# a201-kill-eq.net
KiCad netlist of a schematic drawn in EAGLE
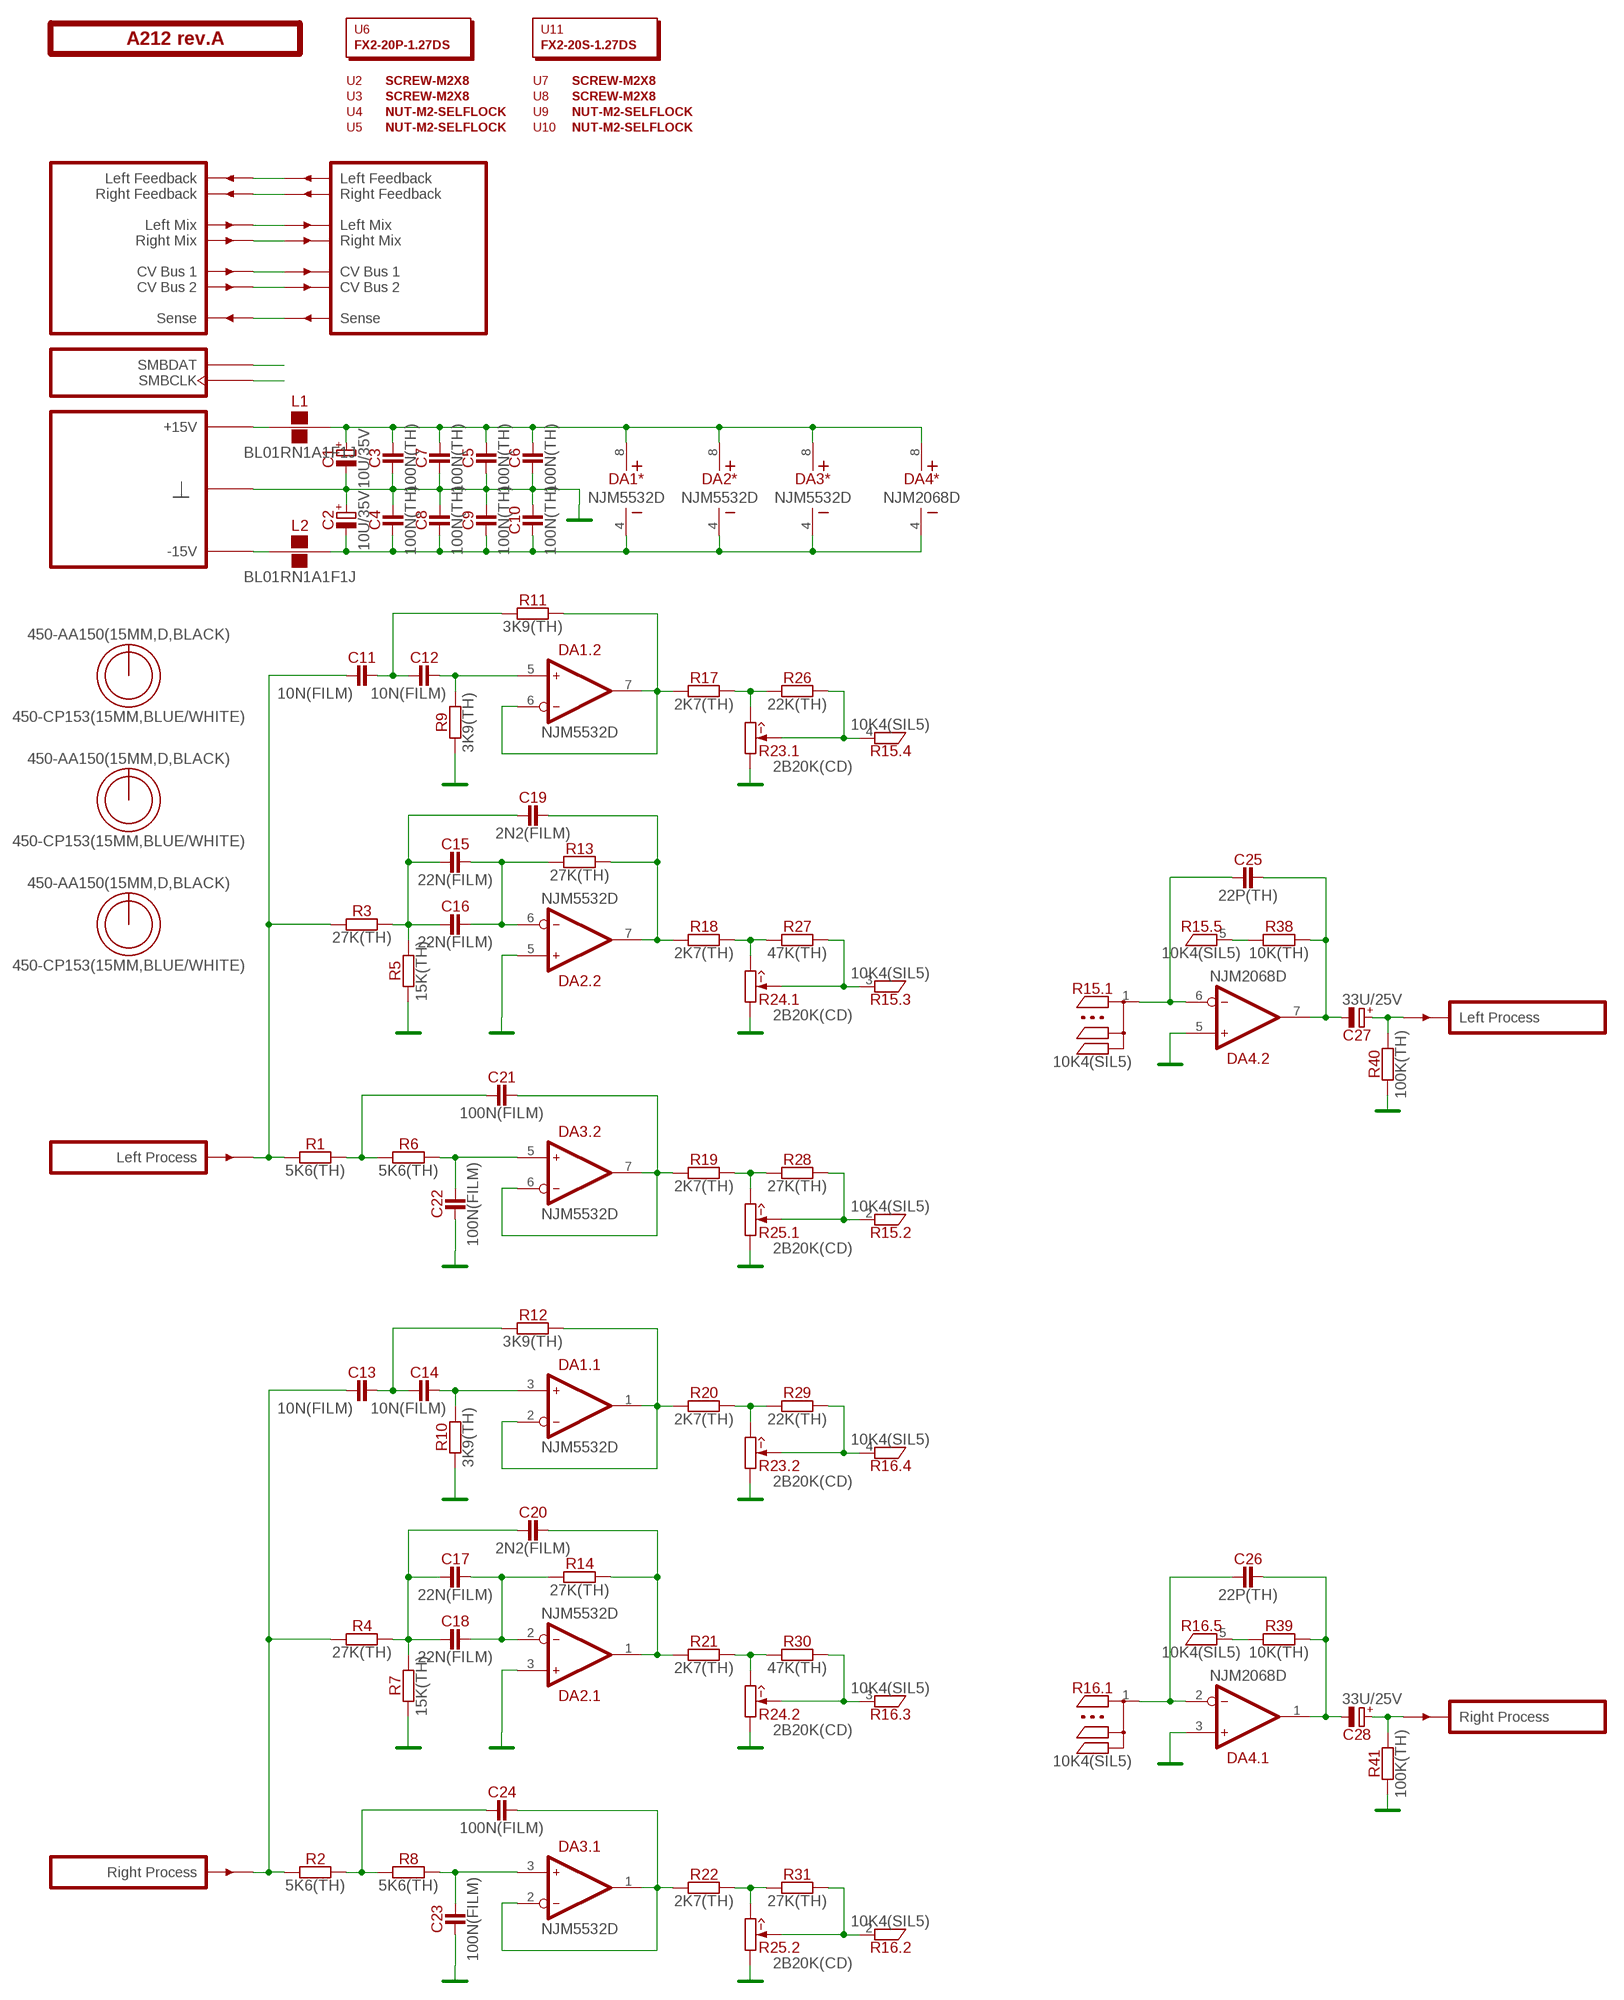
[diagram p0: schematic, sheet 1]

(export (version "E")
  (design (tool "Eeschema 10.0.6"))
  (components
    (comp (ref "C1")
      (value "10U/35V")
      (footprint "eagle-import:E2-5")
      (libsource (lib "eagle-import") (part "?10U/35V"))
    )
    (comp (ref "C2")
      (value "10U/35V")
      (footprint "eagle-import:E2-5")
      (libsource (lib "eagle-import") (part "?10U/35V"))
    )
    (comp (ref "C3")
      (value "100N(TH)")
      (footprint "eagle-import:C050-024X044")
      (libsource (lib "eagle-import") (part "?100N(TH)"))
    )
    (comp (ref "C4")
      (value "100N(TH)")
      (footprint "eagle-import:C050-024X044")
      (libsource (lib "eagle-import") (part "?100N(TH)"))
    )
    (comp (ref "C5")
      (value "100N(TH)")
      (footprint "eagle-import:C050-024X044")
      (libsource (lib "eagle-import") (part "?100N(TH)"))
    )
    (comp (ref "C6")
      (value "100N(TH)")
      (footprint "eagle-import:C050-024X044")
      (libsource (lib "eagle-import") (part "?100N(TH)"))
    )
    (comp (ref "C7")
      (value "100N(TH)")
      (footprint "eagle-import:C050-024X044")
      (libsource (lib "eagle-import") (part "?100N(TH)"))
    )
    (comp (ref "C8")
      (value "100N(TH)")
      (footprint "eagle-import:C050-024X044")
      (libsource (lib "eagle-import") (part "?100N(TH)"))
    )
    (comp (ref "C9")
      (value "100N(TH)")
      (footprint "eagle-import:C050-024X044")
      (libsource (lib "eagle-import") (part "?100N(TH)"))
    )
    (comp (ref "C10")
      (value "100N(TH)")
      (footprint "eagle-import:C050-024X044")
      (libsource (lib "eagle-import") (part "?100N(TH)"))
    )
    (comp (ref "C11")
      (value "10N(FILM)")
      (footprint "eagle-import:C050-025X075")
      (libsource (lib "eagle-import") (part "?10N(FILM)"))
    )
    (comp (ref "C12")
      (value "10N(FILM)")
      (footprint "eagle-import:C050-025X075")
      (libsource (lib "eagle-import") (part "?10N(FILM)"))
    )
    (comp (ref "C13")
      (value "10N(FILM)")
      (footprint "eagle-import:C050-025X075")
      (libsource (lib "eagle-import") (part "?10N(FILM)"))
    )
    (comp (ref "C14")
      (value "10N(FILM)")
      (footprint "eagle-import:C050-025X075")
      (libsource (lib "eagle-import") (part "?10N(FILM)"))
    )
    (comp (ref "C15")
      (value "22N(FILM)")
      (footprint "eagle-import:C050-025X075")
      (libsource (lib "eagle-import") (part "?22N(FILM)"))
    )
    (comp (ref "C16")
      (value "22N(FILM)")
      (footprint "eagle-import:C050-025X075")
      (libsource (lib "eagle-import") (part "?22N(FILM)"))
    )
    (comp (ref "C17")
      (value "22N(FILM)")
      (footprint "eagle-import:C050-025X075")
      (libsource (lib "eagle-import") (part "?22N(FILM)"))
    )
    (comp (ref "C18")
      (value "22N(FILM)")
      (footprint "eagle-import:C050-025X075")
      (libsource (lib "eagle-import") (part "?22N(FILM)"))
    )
    (comp (ref "C19")
      (value "2N2(FILM)")
      (footprint "eagle-import:C050-025X075")
      (libsource (lib "eagle-import") (part "?2N2(FILM)"))
    )
    (comp (ref "C20")
      (value "2N2(FILM)")
      (footprint "eagle-import:C050-025X075")
      (libsource (lib "eagle-import") (part "?2N2(FILM)"))
    )
    (comp (ref "C21")
      (value "100N(FILM)")
      (footprint "eagle-import:C050-025X075")
      (libsource (lib "eagle-import") (part "?100N(FILM)"))
    )
    (comp (ref "C22")
      (value "100N(FILM)")
      (footprint "eagle-import:C050-025X075")
      (libsource (lib "eagle-import") (part "?100N(FILM)"))
    )
    (comp (ref "C23")
      (value "100N(FILM)")
      (footprint "eagle-import:C050-025X075")
      (libsource (lib "eagle-import") (part "?100N(FILM)"))
    )
    (comp (ref "C24")
      (value "100N(FILM)")
      (footprint "eagle-import:C050-025X075")
      (libsource (lib "eagle-import") (part "?100N(FILM)"))
    )
    (comp (ref "C25")
      (value "22P(TH)")
      (footprint "eagle-import:C050-024X044")
      (libsource (lib "eagle-import") (part "?22P(TH)"))
    )
    (comp (ref "C26")
      (value "22P(TH)")
      (footprint "eagle-import:C050-024X044")
      (libsource (lib "eagle-import") (part "?22P(TH)"))
    )
    (comp (ref "C27")
      (value "33U/25V")
      (footprint "eagle-import:E2,5-7")
      (libsource (lib "eagle-import") (part "?33U/25V"))
    )
    (comp (ref "C28")
      (value "33U/25V")
      (footprint "eagle-import:E2,5-7")
      (libsource (lib "eagle-import") (part "?33U/25V"))
    )
    (comp (ref "DA1")
      (value "NJM5532D")
      (footprint "eagle-import:DIP-8")
      (libsource (lib "eagle-import") (part "NJM5532D"))
    )
    (comp (ref "DA2")
      (value "NJM5532D")
      (footprint "eagle-import:DIP-8")
      (libsource (lib "eagle-import") (part "NJM5532D"))
    )
    (comp (ref "DA3")
      (value "NJM5532D")
      (footprint "eagle-import:DIP-8")
      (libsource (lib "eagle-import") (part "NJM5532D"))
    )
    (comp (ref "DA4")
      (value "NJM2068D")
      (footprint "eagle-import:DIP-8")
      (libsource (lib "eagle-import") (part "NJM2068D"))
    )
    (comp (ref "L1")
      (value "BL01RN1A1F1J")
      (footprint "eagle-import:BL01RN1A")
      (libsource (lib "eagle-import") (part "BL01RN1A?1F1J"))
    )
    (comp (ref "L2")
      (value "BL01RN1A1F1J")
      (footprint "eagle-import:BL01RN1A")
      (libsource (lib "eagle-import") (part "BL01RN1A?1F1J"))
    )
    (comp (ref "O1")
      (value "450-AA150(15MM,D,BLACK)")
      (footprint "eagle-import:EMPTY")
      (libsource (lib "eagle-import") (part "450-AA?150(15MM,D,BLACK)"))
    )
    (comp (ref "O2")
      (value "450-AA150(15MM,D,BLACK)")
      (footprint "eagle-import:EMPTY")
      (libsource (lib "eagle-import") (part "450-AA?150(15MM,D,BLACK)"))
    )
    (comp (ref "O3")
      (value "450-AA150(15MM,D,BLACK)")
      (footprint "eagle-import:EMPTY")
      (libsource (lib "eagle-import") (part "450-AA?150(15MM,D,BLACK)"))
    )
    (comp (ref "O4")
      (value "450-CP153(15MM,BLUE/WHITE)")
      (footprint "eagle-import:EMPTY")
      (libsource (lib "eagle-import") (part "450-C?P153(15MM,BLUE/WHITE)"))
    )
    (comp (ref "O5")
      (value "450-CP153(15MM,BLUE/WHITE)")
      (footprint "eagle-import:EMPTY")
      (libsource (lib "eagle-import") (part "450-C?P153(15MM,BLUE/WHITE)"))
    )
    (comp (ref "O6")
      (value "450-CP153(15MM,BLUE/WHITE)")
      (footprint "eagle-import:EMPTY")
      (libsource (lib "eagle-import") (part "450-C?P153(15MM,BLUE/WHITE)"))
    )
    (comp (ref "PCB1")
      (value "A212 rev.A")
      (footprint "eagle-import:ST2-BOARD-50")
      (libsource (lib "eagle-import") (part "ST2-BOARD-?50"))
    )
    (comp (ref "R1")
      (value "5K6(TH)")
      (footprint "eagle-import:R-0207_10")
      (libsource (lib "eagle-import") (part "?5K6(TH)"))
    )
    (comp (ref "R2")
      (value "5K6(TH)")
      (footprint "eagle-import:R-0207_10")
      (libsource (lib "eagle-import") (part "?5K6(TH)"))
    )
    (comp (ref "R3")
      (value "27K(TH)")
      (footprint "eagle-import:R-0207_10")
      (libsource (lib "eagle-import") (part "?27K(TH)"))
    )
    (comp (ref "R4")
      (value "27K(TH)")
      (footprint "eagle-import:R-0207_10")
      (libsource (lib "eagle-import") (part "?27K(TH)"))
    )
    (comp (ref "R5")
      (value "15K(TH)")
      (footprint "eagle-import:R-0207_10")
      (libsource (lib "eagle-import") (part "?15K(TH)"))
    )
    (comp (ref "R6")
      (value "5K6(TH)")
      (footprint "eagle-import:R-0207_10")
      (libsource (lib "eagle-import") (part "?5K6(TH)"))
    )
    (comp (ref "R7")
      (value "15K(TH)")
      (footprint "eagle-import:R-0207_10")
      (libsource (lib "eagle-import") (part "?15K(TH)"))
    )
    (comp (ref "R8")
      (value "5K6(TH)")
      (footprint "eagle-import:R-0207_10")
      (libsource (lib "eagle-import") (part "?5K6(TH)"))
    )
    (comp (ref "R9")
      (value "3K9(TH)")
      (footprint "eagle-import:R-0207_10")
      (libsource (lib "eagle-import") (part "?3K9(TH)"))
    )
    (comp (ref "R10")
      (value "3K9(TH)")
      (footprint "eagle-import:R-0207_10")
      (libsource (lib "eagle-import") (part "?3K9(TH)"))
    )
    (comp (ref "R11")
      (value "3K9(TH)")
      (footprint "eagle-import:R-0207_10")
      (libsource (lib "eagle-import") (part "?3K9(TH)"))
    )
    (comp (ref "R12")
      (value "3K9(TH)")
      (footprint "eagle-import:R-0207_10")
      (libsource (lib "eagle-import") (part "?3K9(TH)"))
    )
    (comp (ref "R13")
      (value "27K(TH)")
      (footprint "eagle-import:R-0207_10")
      (libsource (lib "eagle-import") (part "?27K(TH)"))
    )
    (comp (ref "R14")
      (value "27K(TH)")
      (footprint "eagle-import:R-0207_10")
      (libsource (lib "eagle-import") (part "?27K(TH)"))
    )
    (comp (ref "R15")
      (value "10K4(SIL5)")
      (footprint "eagle-import:R-SIL5")
      (libsource (lib "eagle-import") (part "?4(SIL5)10K"))
    )
    (comp (ref "R16")
      (value "10K4(SIL5)")
      (footprint "eagle-import:R-SIL5")
      (libsource (lib "eagle-import") (part "?4(SIL5)10K"))
    )
    (comp (ref "R17")
      (value "2K7(TH)")
      (footprint "eagle-import:R-0207_10")
      (libsource (lib "eagle-import") (part "?2K7(TH)"))
    )
    (comp (ref "R18")
      (value "2K7(TH)")
      (footprint "eagle-import:R-0207_10")
      (libsource (lib "eagle-import") (part "?2K7(TH)"))
    )
    (comp (ref "R19")
      (value "2K7(TH)")
      (footprint "eagle-import:R-0207_10")
      (libsource (lib "eagle-import") (part "?2K7(TH)"))
    )
    (comp (ref "R20")
      (value "2K7(TH)")
      (footprint "eagle-import:R-0207_10")
      (libsource (lib "eagle-import") (part "?2K7(TH)"))
    )
    (comp (ref "R21")
      (value "2K7(TH)")
      (footprint "eagle-import:R-0207_10")
      (libsource (lib "eagle-import") (part "?2K7(TH)"))
    )
    (comp (ref "R22")
      (value "2K7(TH)")
      (footprint "eagle-import:R-0207_10")
      (libsource (lib "eagle-import") (part "?2K7(TH)"))
    )
    (comp (ref "R23")
      (value "2B20K(CD)")
      (footprint "eagle-import:RV11-DUAL")
      (libsource (lib "eagle-import") (part "2?B20K(CD)"))
    )
    (comp (ref "R24")
      (value "2B20K(CD)")
      (footprint "eagle-import:RV11-DUAL")
      (libsource (lib "eagle-import") (part "2?B20K(CD)"))
    )
    (comp (ref "R25")
      (value "2B20K(CD)")
      (footprint "eagle-import:RV11-DUAL")
      (libsource (lib "eagle-import") (part "2?B20K(CD)"))
    )
    (comp (ref "R26")
      (value "22K(TH)")
      (footprint "eagle-import:R-0207_10")
      (libsource (lib "eagle-import") (part "?22K(TH)"))
    )
    (comp (ref "R27")
      (value "47K(TH)")
      (footprint "eagle-import:R-0207_10")
      (libsource (lib "eagle-import") (part "?47K(TH)"))
    )
    (comp (ref "R28")
      (value "27K(TH)")
      (footprint "eagle-import:R-0207_10")
      (libsource (lib "eagle-import") (part "?27K(TH)"))
    )
    (comp (ref "R29")
      (value "22K(TH)")
      (footprint "eagle-import:R-0207_10")
      (libsource (lib "eagle-import") (part "?22K(TH)"))
    )
    (comp (ref "R30")
      (value "47K(TH)")
      (footprint "eagle-import:R-0207_10")
      (libsource (lib "eagle-import") (part "?47K(TH)"))
    )
    (comp (ref "R31")
      (value "27K(TH)")
      (footprint "eagle-import:R-0207_10")
      (libsource (lib "eagle-import") (part "?27K(TH)"))
    )
    (comp (ref "R38")
      (value "10K(TH)")
      (footprint "eagle-import:R-0207_10")
      (libsource (lib "eagle-import") (part "?10K(TH)"))
    )
    (comp (ref "R39")
      (value "10K(TH)")
      (footprint "eagle-import:R-0207_10")
      (libsource (lib "eagle-import") (part "?10K(TH)"))
    )
    (comp (ref "R40")
      (value "100K(TH)")
      (footprint "eagle-import:R-0207_10")
      (libsource (lib "eagle-import") (part "?100K(TH)"))
    )
    (comp (ref "R41")
      (value "100K(TH)")
      (footprint "eagle-import:R-0207_10")
      (libsource (lib "eagle-import") (part "?100K(TH)"))
    )
    (comp (ref "U2")
      (value "SCREW-M2X8")
      (footprint "eagle-import:EMPTY")
      (libsource (lib "eagle-import") (part "?SCREW-M2X8"))
    )
    (comp (ref "U3")
      (value "SCREW-M2X8")
      (footprint "eagle-import:EMPTY")
      (libsource (lib "eagle-import") (part "?SCREW-M2X8"))
    )
    (comp (ref "U4")
      (value "NUT-M2-SELFLOCK")
      (footprint "eagle-import:EMPTY")
      (libsource (lib "eagle-import") (part "?NUT-M2-SELFLOCK"))
    )
    (comp (ref "U5")
      (value "NUT-M2-SELFLOCK")
      (footprint "eagle-import:EMPTY")
      (libsource (lib "eagle-import") (part "?NUT-M2-SELFLOCK"))
    )
    (comp (ref "U6")
      (value "FX2-20P-1.27DS")
      (footprint "eagle-import:EMPTY")
      (libsource (lib "eagle-import") (part "?FX2-20P-1.27DS"))
    )
    (comp (ref "U7")
      (value "SCREW-M2X8")
      (footprint "eagle-import:EMPTY")
      (libsource (lib "eagle-import") (part "?SCREW-M2X8"))
    )
    (comp (ref "U8")
      (value "SCREW-M2X8")
      (footprint "eagle-import:EMPTY")
      (libsource (lib "eagle-import") (part "?SCREW-M2X8"))
    )
    (comp (ref "U9")
      (value "NUT-M2-SELFLOCK")
      (footprint "eagle-import:EMPTY")
      (libsource (lib "eagle-import") (part "?NUT-M2-SELFLOCK"))
    )
    (comp (ref "U10")
      (value "NUT-M2-SELFLOCK")
      (footprint "eagle-import:EMPTY")
      (libsource (lib "eagle-import") (part "?NUT-M2-SELFLOCK"))
    )
    (comp (ref "U11")
      (value "FX2-20S-1.27DS")
      (footprint "eagle-import:EMPTY")
      (libsource (lib "eagle-import") (part "?FX2-20S-1.27DS"))
    )
  )
  (nets
    (net (code "1") (name "GND") (class "Default")
      (node (ref "C1") (pin "-") (pinfunction "-_-") (pintype "passive"))
      (node (ref "C10") (pin "2") (pinfunction "2_2") (pintype "passive"))
      (node (ref "C2") (pin "+") (pinfunction "+_+") (pintype "passive"))
      (node (ref "C22") (pin "1") (pinfunction "1_1") (pintype "passive"))
      (node (ref "C23") (pin "1") (pinfunction "1_1") (pintype "passive"))
      (node (ref "C3") (pin "1") (pinfunction "1_1") (pintype "passive"))
      (node (ref "C4") (pin "2") (pinfunction "2_2") (pintype "passive"))
      (node (ref "C5") (pin "1") (pinfunction "1_1") (pintype "passive"))
      (node (ref "C6") (pin "1") (pinfunction "1_1") (pintype "passive"))
      (node (ref "C7") (pin "1") (pinfunction "1_1") (pintype "passive"))
      (node (ref "C8") (pin "2") (pinfunction "2_2") (pintype "passive"))
      (node (ref "C9") (pin "2") (pinfunction "2_2") (pintype "passive"))
      (node (ref "DA2") (pin "3") (pinfunction "IN+_3") (pintype "input"))
      (node (ref "DA2") (pin "5") (pinfunction "IN+_5") (pintype "input"))
      (node (ref "DA4") (pin "3") (pinfunction "IN+_3") (pintype "input"))
      (node (ref "DA4") (pin "5") (pinfunction "IN+_5") (pintype "input"))
      (node (ref "PCB1") (pin "B4") (pinfunction "GND_B4") (pintype "bidirectional"))
      (node (ref "PCB1") (pin "B4'") (pinfunction "GND_B4'") (pintype "bidirectional"))
      (node (ref "PCB1") (pin "B5") (pinfunction "GND_B5") (pintype "bidirectional"))
      (node (ref "PCB1") (pin "B5'") (pinfunction "GND_B5'") (pintype "bidirectional"))
      (node (ref "PCB1") (pin "B6") (pinfunction "GND_B6") (pintype "bidirectional"))
      (node (ref "PCB1") (pin "B6'") (pinfunction "GND_B6'") (pintype "bidirectional"))
      (node (ref "PCB1") (pin "B7") (pinfunction "GND_B7") (pintype "bidirectional"))
      (node (ref "PCB1") (pin "B7'") (pinfunction "GND_B7'") (pintype "bidirectional"))
      (node (ref "PCB1") (pin "B8") (pinfunction "GND_B8") (pintype "bidirectional"))
      (node (ref "PCB1") (pin "B8'") (pinfunction "GND_B8'") (pintype "bidirectional"))
      (node (ref "R10") (pin "1") (pinfunction "1_1") (pintype "passive"))
      (node (ref "R23") (pin "1") (pinfunction "CCW_1") (pintype "passive"))
      (node (ref "R23") (pin "1'") (pinfunction "CCW_1'") (pintype "passive"))
      (node (ref "R24") (pin "1") (pinfunction "CCW_1") (pintype "passive"))
      (node (ref "R24") (pin "1'") (pinfunction "CCW_1'") (pintype "passive"))
      (node (ref "R25") (pin "1") (pinfunction "CCW_1") (pintype "passive"))
      (node (ref "R25") (pin "1'") (pinfunction "CCW_1'") (pintype "passive"))
      (node (ref "R40") (pin "1") (pinfunction "1_1") (pintype "passive"))
      (node (ref "R41") (pin "1") (pinfunction "1_1") (pintype "passive"))
      (node (ref "R5") (pin "1") (pinfunction "1_1") (pintype "passive"))
      (node (ref "R7") (pin "1") (pinfunction "1_1") (pintype "passive"))
      (node (ref "R9") (pin "1") (pinfunction "1_1") (pintype "passive"))
    )
    (net (code "2") (name "Net-(C11-Pad2)") (class "Default")
      (node (ref "C11") (pin "2") (pinfunction "2_2") (pintype "passive"))
      (node (ref "C12") (pin "1") (pinfunction "1_1") (pintype "passive"))
      (node (ref "R11") (pin "1") (pinfunction "1_1") (pintype "passive"))
    )
    (net (code "3") (name "Net-(C13-Pad2)") (class "Default")
      (node (ref "C13") (pin "2") (pinfunction "2_2") (pintype "passive"))
      (node (ref "C14") (pin "1") (pinfunction "1_1") (pintype "passive"))
      (node (ref "R12") (pin "1") (pinfunction "1_1") (pintype "passive"))
    )
    (net (code "4") (name "Net-(C15-Pad1)") (class "Default")
      (node (ref "C15") (pin "1") (pinfunction "1_1") (pintype "passive"))
      (node (ref "C16") (pin "1") (pinfunction "1_1") (pintype "passive"))
      (node (ref "C19") (pin "1") (pinfunction "1_1") (pintype "passive"))
      (node (ref "R3") (pin "2") (pinfunction "2_2") (pintype "passive"))
      (node (ref "R5") (pin "2") (pinfunction "2_2") (pintype "passive"))
    )
    (net (code "5") (name "Net-(C17-Pad1)") (class "Default")
      (node (ref "C17") (pin "1") (pinfunction "1_1") (pintype "passive"))
      (node (ref "C18") (pin "1") (pinfunction "1_1") (pintype "passive"))
      (node (ref "C20") (pin "1") (pinfunction "1_1") (pintype "passive"))
      (node (ref "R4") (pin "2") (pinfunction "2_2") (pintype "passive"))
      (node (ref "R7") (pin "2") (pinfunction "2_2") (pintype "passive"))
    )
    (net (code "6") (name "Net-(C21-Pad1)") (class "Default")
      (node (ref "C21") (pin "1") (pinfunction "1_1") (pintype "passive"))
      (node (ref "R1") (pin "2") (pinfunction "2_2") (pintype "passive"))
      (node (ref "R6") (pin "1") (pinfunction "1_1") (pintype "passive"))
    )
    (net (code "7") (name "Net-(C24-Pad1)") (class "Default")
      (node (ref "C24") (pin "1") (pinfunction "1_1") (pintype "passive"))
      (node (ref "R2") (pin "2") (pinfunction "2_2") (pintype "passive"))
      (node (ref "R8") (pin "1") (pinfunction "1_1") (pintype "passive"))
    )
    (net (code "8") (name "Net-(DA1A-V+)") (class "Default")
      (node (ref "C1") (pin "+") (pinfunction "+_+") (pintype "passive"))
      (node (ref "C3") (pin "2") (pinfunction "2_2") (pintype "passive"))
      (node (ref "C5") (pin "2") (pinfunction "2_2") (pintype "passive"))
      (node (ref "C6") (pin "2") (pinfunction "2_2") (pintype "passive"))
      (node (ref "C7") (pin "2") (pinfunction "2_2") (pintype "passive"))
      (node (ref "DA1") (pin "8") (pinfunction "V+_8") (pintype "power_in"))
      (node (ref "DA2") (pin "8") (pinfunction "V+_8") (pintype "power_in"))
      (node (ref "DA3") (pin "8") (pinfunction "V+_8") (pintype "power_in"))
      (node (ref "DA4") (pin "8") (pinfunction "V+_8") (pintype "power_in"))
      (node (ref "L1") (pin "2") (pinfunction "2_2") (pintype "passive"))
    )
    (net (code "9") (name "Net-(DA1A-V-)") (class "Default")
      (node (ref "C10") (pin "1") (pinfunction "1_1") (pintype "passive"))
      (node (ref "C2") (pin "-") (pinfunction "-_-") (pintype "passive"))
      (node (ref "C4") (pin "1") (pinfunction "1_1") (pintype "passive"))
      (node (ref "C8") (pin "1") (pinfunction "1_1") (pintype "passive"))
      (node (ref "C9") (pin "1") (pinfunction "1_1") (pintype "passive"))
      (node (ref "DA1") (pin "4") (pinfunction "V-_4") (pintype "power_in"))
      (node (ref "DA2") (pin "4") (pinfunction "V-_4") (pintype "power_in"))
      (node (ref "DA3") (pin "4") (pinfunction "V-_4") (pintype "power_in"))
      (node (ref "DA4") (pin "4") (pinfunction "V-_4") (pintype "power_in"))
      (node (ref "L2") (pin "2") (pinfunction "2_2") (pintype "passive"))
    )
    (net (code "10") (name "Net-(DA1B-IN+)") (class "Default")
      (node (ref "C14") (pin "2") (pinfunction "2_2") (pintype "passive"))
      (node (ref "DA1") (pin "3") (pinfunction "IN+_3") (pintype "input"))
      (node (ref "R10") (pin "2") (pinfunction "2_2") (pintype "passive"))
    )
    (net (code "11") (name "Net-(DA1B-IN-)") (class "Default")
      (node (ref "DA1") (pin "1") (pinfunction "OUT_1") (pintype "output"))
      (node (ref "DA1") (pin "2") (pinfunction "IN-_2") (pintype "input"))
      (node (ref "R12") (pin "2") (pinfunction "2_2") (pintype "passive"))
      (node (ref "R20") (pin "1") (pinfunction "1_1") (pintype "passive"))
    )
    (net (code "12") (name "Net-(DA1C-IN+)") (class "Default")
      (node (ref "C12") (pin "2") (pinfunction "2_2") (pintype "passive"))
      (node (ref "DA1") (pin "5") (pinfunction "IN+_5") (pintype "input"))
      (node (ref "R9") (pin "2") (pinfunction "2_2") (pintype "passive"))
    )
    (net (code "13") (name "Net-(DA1C-IN-)") (class "Default")
      (node (ref "DA1") (pin "6") (pinfunction "IN-_6") (pintype "input"))
      (node (ref "DA1") (pin "7") (pinfunction "OUT_7") (pintype "output"))
      (node (ref "R11") (pin "2") (pinfunction "2_2") (pintype "passive"))
      (node (ref "R17") (pin "1") (pinfunction "1_1") (pintype "passive"))
    )
    (net (code "14") (name "Net-(DA2B-IN-)") (class "Default")
      (node (ref "C17") (pin "2") (pinfunction "2_2") (pintype "passive"))
      (node (ref "C18") (pin "2") (pinfunction "2_2") (pintype "passive"))
      (node (ref "DA2") (pin "2") (pinfunction "IN-_2") (pintype "input"))
      (node (ref "R14") (pin "1") (pinfunction "1_1") (pintype "passive"))
    )
    (net (code "15") (name "Net-(DA2B-OUT)") (class "Default")
      (node (ref "C20") (pin "2") (pinfunction "2_2") (pintype "passive"))
      (node (ref "DA2") (pin "1") (pinfunction "OUT_1") (pintype "output"))
      (node (ref "R14") (pin "2") (pinfunction "2_2") (pintype "passive"))
      (node (ref "R21") (pin "1") (pinfunction "1_1") (pintype "passive"))
    )
    (net (code "16") (name "Net-(DA2C-IN-)") (class "Default")
      (node (ref "C15") (pin "2") (pinfunction "2_2") (pintype "passive"))
      (node (ref "C16") (pin "2") (pinfunction "2_2") (pintype "passive"))
      (node (ref "DA2") (pin "6") (pinfunction "IN-_6") (pintype "input"))
      (node (ref "R13") (pin "1") (pinfunction "1_1") (pintype "passive"))
    )
    (net (code "17") (name "Net-(DA2C-OUT)") (class "Default")
      (node (ref "C19") (pin "2") (pinfunction "2_2") (pintype "passive"))
      (node (ref "DA2") (pin "7") (pinfunction "OUT_7") (pintype "output"))
      (node (ref "R13") (pin "2") (pinfunction "2_2") (pintype "passive"))
      (node (ref "R18") (pin "1") (pinfunction "1_1") (pintype "passive"))
    )
    (net (code "18") (name "Net-(DA3B-IN+)") (class "Default")
      (node (ref "C23") (pin "2") (pinfunction "2_2") (pintype "passive"))
      (node (ref "DA3") (pin "3") (pinfunction "IN+_3") (pintype "input"))
      (node (ref "R8") (pin "2") (pinfunction "2_2") (pintype "passive"))
    )
    (net (code "19") (name "Net-(DA3B-IN-)") (class "Default")
      (node (ref "C24") (pin "2") (pinfunction "2_2") (pintype "passive"))
      (node (ref "DA3") (pin "1") (pinfunction "OUT_1") (pintype "output"))
      (node (ref "DA3") (pin "2") (pinfunction "IN-_2") (pintype "input"))
      (node (ref "R22") (pin "1") (pinfunction "1_1") (pintype "passive"))
    )
    (net (code "20") (name "Net-(DA3C-IN+)") (class "Default")
      (node (ref "C22") (pin "2") (pinfunction "2_2") (pintype "passive"))
      (node (ref "DA3") (pin "5") (pinfunction "IN+_5") (pintype "input"))
      (node (ref "R6") (pin "2") (pinfunction "2_2") (pintype "passive"))
    )
    (net (code "21") (name "Net-(DA3C-IN-)") (class "Default")
      (node (ref "C21") (pin "2") (pinfunction "2_2") (pintype "passive"))
      (node (ref "DA3") (pin "6") (pinfunction "IN-_6") (pintype "input"))
      (node (ref "DA3") (pin "7") (pinfunction "OUT_7") (pintype "output"))
      (node (ref "R19") (pin "1") (pinfunction "1_1") (pintype "passive"))
    )
    (net (code "22") (name "Net-(DA4B-IN-)") (class "Default")
      (node (ref "C26") (pin "1") (pinfunction "1_1") (pintype "passive"))
      (node (ref "DA4") (pin "2") (pinfunction "IN-_2") (pintype "input"))
      (node (ref "R16") (pin "1") (pinfunction "R_1") (pintype "passive"))
    )
    (net (code "23") (name "Net-(DA4B-OUT)") (class "Default")
      (node (ref "C26") (pin "2") (pinfunction "2_2") (pintype "passive"))
      (node (ref "C28") (pin "-") (pinfunction "-_-") (pintype "passive"))
      (node (ref "DA4") (pin "1") (pinfunction "OUT_1") (pintype "output"))
      (node (ref "R39") (pin "2") (pinfunction "2_2") (pintype "passive"))
    )
    (net (code "24") (name "Net-(DA4C-IN-)") (class "Default")
      (node (ref "C25") (pin "1") (pinfunction "1_1") (pintype "passive"))
      (node (ref "DA4") (pin "6") (pinfunction "IN-_6") (pintype "input"))
      (node (ref "R15") (pin "1") (pinfunction "R_1") (pintype "passive"))
    )
    (net (code "25") (name "Net-(DA4C-OUT)") (class "Default")
      (node (ref "C25") (pin "2") (pinfunction "2_2") (pintype "passive"))
      (node (ref "C27") (pin "-") (pinfunction "-_-") (pintype "passive"))
      (node (ref "DA4") (pin "7") (pinfunction "OUT_7") (pintype "output"))
      (node (ref "R38") (pin "2") (pinfunction "2_2") (pintype "passive"))
    )
    (net (code "26") (name "Net-(L1-Pad1)") (class "Default")
      (node (ref "L1") (pin "1") (pinfunction "1_1") (pintype "passive"))
      (node (ref "PCB1") (pin "A+15") (pinfunction "P+15V_A+15") (pintype "bidirectional"))
      (node (ref "PCB1") (pin "A+15'") (pinfunction "P+15V_A+15'") (pintype "bidirectional"))
      (node (ref "PCB1") (pin "B+15") (pinfunction "P+15V_B+15") (pintype "bidirectional"))
      (node (ref "PCB1") (pin "B+15'") (pinfunction "P+15V_B+15'") (pintype "bidirectional"))
    )
    (net (code "27") (name "Net-(L2-Pad1)") (class "Default")
      (node (ref "L2") (pin "1") (pinfunction "1_1") (pintype "passive"))
      (node (ref "PCB1") (pin "A-15") (pinfunction "P-15V_A-15") (pintype "bidirectional"))
      (node (ref "PCB1") (pin "A-15'") (pinfunction "P-15V_A-15'") (pintype "bidirectional"))
      (node (ref "PCB1") (pin "B-15") (pinfunction "P-15V_B-15") (pintype "bidirectional"))
      (node (ref "PCB1") (pin "B-15'") (pinfunction "P-15V_B-15'") (pintype "bidirectional"))
    )
    (net (code "28") (name "Net-(PCB1B-INL)") (class "Default")
      (node (ref "C11") (pin "1") (pinfunction "1_1") (pintype "passive"))
      (node (ref "PCB1") (pin "BINL") (pinfunction "INL_BINL") (pintype "bidirectional"))
      (node (ref "R1") (pin "1") (pinfunction "1_1") (pintype "passive"))
      (node (ref "R3") (pin "1") (pinfunction "1_1") (pintype "passive"))
    )
    (net (code "29") (name "Net-(PCB1C-INR)") (class "Default")
      (node (ref "C13") (pin "1") (pinfunction "1_1") (pintype "passive"))
      (node (ref "PCB1") (pin "BINR") (pinfunction "INR_BINR") (pintype "bidirectional"))
      (node (ref "R2") (pin "1") (pinfunction "1_1") (pintype "passive"))
      (node (ref "R4") (pin "1") (pinfunction "1_1") (pintype "passive"))
    )
    (net (code "30") (name "Net-(PCB1D-OUTL)") (class "Default")
      (node (ref "C27") (pin "+") (pinfunction "+_+") (pintype "passive"))
      (node (ref "PCB1") (pin "BOUTL'") (pinfunction "OUTL_BOUTL'") (pintype "bidirectional"))
      (node (ref "R40") (pin "2") (pinfunction "2_2") (pintype "passive"))
    )
    (net (code "31") (name "Net-(PCB1E-OUTR)") (class "Default")
      (node (ref "C28") (pin "+") (pinfunction "+_+") (pintype "passive"))
      (node (ref "PCB1") (pin "BOUTR'") (pinfunction "OUTR_BOUTR'") (pintype "bidirectional"))
      (node (ref "R41") (pin "2") (pinfunction "2_2") (pintype "passive"))
    )
    (net (code "32") (name "Net-(PCB1F-CV1)") (class "Default")
      (node (ref "PCB1") (pin "ACV1") (pinfunction "CV1_ACV1") (pintype "bidirectional"))
      (node (ref "PCB1") (pin "ACV1'") (pinfunction "CV1'_ACV1'") (pintype "bidirectional"))
    )
    (net (code "33") (name "Net-(PCB1F-CV2)") (class "Default")
      (node (ref "PCB1") (pin "ACV2") (pinfunction "CV2_ACV2") (pintype "bidirectional"))
      (node (ref "PCB1") (pin "ACV2'") (pinfunction "CV2'_ACV2'") (pintype "bidirectional"))
    )
    (net (code "34") (name "Net-(PCB1F-LFBK)") (class "Default")
      (node (ref "PCB1") (pin "ALFBK") (pinfunction "LFBK_ALFBK") (pintype "bidirectional"))
      (node (ref "PCB1") (pin "ALFBK'") (pinfunction "LFBK'_ALFBK'") (pintype "bidirectional"))
    )
    (net (code "35") (name "Net-(PCB1F-LMIX)") (class "Default")
      (node (ref "PCB1") (pin "ALMIX") (pinfunction "LMIX_ALMIX") (pintype "bidirectional"))
      (node (ref "PCB1") (pin "ALMIX'") (pinfunction "LMIX'_ALMIX'") (pintype "bidirectional"))
    )
    (net (code "36") (name "Net-(PCB1F-RFBK)") (class "Default")
      (node (ref "PCB1") (pin "ARFBK") (pinfunction "RFBK_ARFBK") (pintype "bidirectional"))
      (node (ref "PCB1") (pin "ARFBK'") (pinfunction "RFBK'_ARFBK'") (pintype "bidirectional"))
    )
    (net (code "37") (name "Net-(PCB1F-RMIX)") (class "Default")
      (node (ref "PCB1") (pin "ARMIX") (pinfunction "RMIX_ARMIX") (pintype "bidirectional"))
      (node (ref "PCB1") (pin "ARMIX'") (pinfunction "RMIX'_ARMIX'") (pintype "bidirectional"))
    )
    (net (code "38") (name "Net-(PCB1F-SENSE)") (class "Default")
      (node (ref "PCB1") (pin "BSENSE") (pinfunction "SENSE_BSENSE") (pintype "bidirectional"))
      (node (ref "PCB1") (pin "BSENSE'") (pinfunction "SENSE'_BSENSE'") (pintype "bidirectional"))
    )
    (net (code "39") (name "Net-(PCB1H-SMBCLK-PadASMBCLK')") (class "Default")
      (node (ref "PCB1") (pin "ASMBCLK") (pinfunction "SMBCLK_ASMBCLK") (pintype "bidirectional"))
      (node (ref "PCB1") (pin "ASMBCLK'") (pinfunction "SMBCLK_ASMBCLK'") (pintype "bidirectional"))
    )
    (net (code "40") (name "Net-(PCB1H-SMBDAT-PadASMBDAT')") (class "Default")
      (node (ref "PCB1") (pin "ASMBDAT") (pinfunction "SMBDAT_ASMBDAT") (pintype "bidirectional"))
      (node (ref "PCB1") (pin "ASMBDAT'") (pinfunction "SMBDAT_ASMBDAT'") (pintype "bidirectional"))
    )
    (net (code "41") (name "Net-(R15B-R)") (class "Default")
      (node (ref "R15") (pin "2") (pinfunction "R_2") (pintype "passive"))
      (node (ref "R25") (pin "2") (pinfunction "W_2") (pintype "passive"))
      (node (ref "R28") (pin "2") (pinfunction "2_2") (pintype "passive"))
    )
    (net (code "42") (name "Net-(R15C-R)") (class "Default")
      (node (ref "R15") (pin "3") (pinfunction "R_3") (pintype "passive"))
      (node (ref "R24") (pin "2") (pinfunction "W_2") (pintype "passive"))
      (node (ref "R27") (pin "2") (pinfunction "2_2") (pintype "passive"))
    )
    (net (code "43") (name "Net-(R15D-R)") (class "Default")
      (node (ref "R15") (pin "4") (pinfunction "R_4") (pintype "passive"))
      (node (ref "R23") (pin "2") (pinfunction "W_2") (pintype "passive"))
      (node (ref "R26") (pin "2") (pinfunction "2_2") (pintype "passive"))
    )
    (net (code "44") (name "Net-(R15E-R)") (class "Default")
      (node (ref "R15") (pin "5") (pinfunction "R_5") (pintype "passive"))
      (node (ref "R38") (pin "1") (pinfunction "1_1") (pintype "passive"))
    )
    (net (code "45") (name "Net-(R16B-R)") (class "Default")
      (node (ref "R16") (pin "2") (pinfunction "R_2") (pintype "passive"))
      (node (ref "R25") (pin "2'") (pinfunction "W_2'") (pintype "passive"))
      (node (ref "R31") (pin "2") (pinfunction "2_2") (pintype "passive"))
    )
    (net (code "46") (name "Net-(R16C-R)") (class "Default")
      (node (ref "R16") (pin "3") (pinfunction "R_3") (pintype "passive"))
      (node (ref "R24") (pin "2'") (pinfunction "W_2'") (pintype "passive"))
      (node (ref "R30") (pin "2") (pinfunction "2_2") (pintype "passive"))
    )
    (net (code "47") (name "Net-(R16D-R)") (class "Default")
      (node (ref "R16") (pin "4") (pinfunction "R_4") (pintype "passive"))
      (node (ref "R23") (pin "2'") (pinfunction "W_2'") (pintype "passive"))
      (node (ref "R29") (pin "2") (pinfunction "2_2") (pintype "passive"))
    )
    (net (code "48") (name "Net-(R16E-R)") (class "Default")
      (node (ref "R16") (pin "5") (pinfunction "R_5") (pintype "passive"))
      (node (ref "R39") (pin "1") (pinfunction "1_1") (pintype "passive"))
    )
    (net (code "49") (name "Net-(R23A-CW)") (class "Default")
      (node (ref "R17") (pin "2") (pinfunction "2_2") (pintype "passive"))
      (node (ref "R23") (pin "3") (pinfunction "CW_3") (pintype "passive"))
      (node (ref "R26") (pin "1") (pinfunction "1_1") (pintype "passive"))
    )
    (net (code "50") (name "Net-(R23B-CW)") (class "Default")
      (node (ref "R20") (pin "2") (pinfunction "2_2") (pintype "passive"))
      (node (ref "R23") (pin "3'") (pinfunction "CW_3'") (pintype "passive"))
      (node (ref "R29") (pin "1") (pinfunction "1_1") (pintype "passive"))
    )
    (net (code "51") (name "Net-(R24A-CW)") (class "Default")
      (node (ref "R18") (pin "2") (pinfunction "2_2") (pintype "passive"))
      (node (ref "R24") (pin "3") (pinfunction "CW_3") (pintype "passive"))
      (node (ref "R27") (pin "1") (pinfunction "1_1") (pintype "passive"))
    )
    (net (code "52") (name "Net-(R24B-CW)") (class "Default")
      (node (ref "R21") (pin "2") (pinfunction "2_2") (pintype "passive"))
      (node (ref "R24") (pin "3'") (pinfunction "CW_3'") (pintype "passive"))
      (node (ref "R30") (pin "1") (pinfunction "1_1") (pintype "passive"))
    )
    (net (code "53") (name "Net-(R25A-CW)") (class "Default")
      (node (ref "R19") (pin "2") (pinfunction "2_2") (pintype "passive"))
      (node (ref "R25") (pin "3") (pinfunction "CW_3") (pintype "passive"))
      (node (ref "R28") (pin "1") (pinfunction "1_1") (pintype "passive"))
    )
    (net (code "54") (name "Net-(R25B-CW)") (class "Default")
      (node (ref "R22") (pin "2") (pinfunction "2_2") (pintype "passive"))
      (node (ref "R25") (pin "3'") (pinfunction "CW_3'") (pintype "passive"))
      (node (ref "R31") (pin "1") (pinfunction "1_1") (pintype "passive"))
    )
  )
)
